# PoE_Si3404.net
KiCad netlist of a schematic drawn in Altium Designer
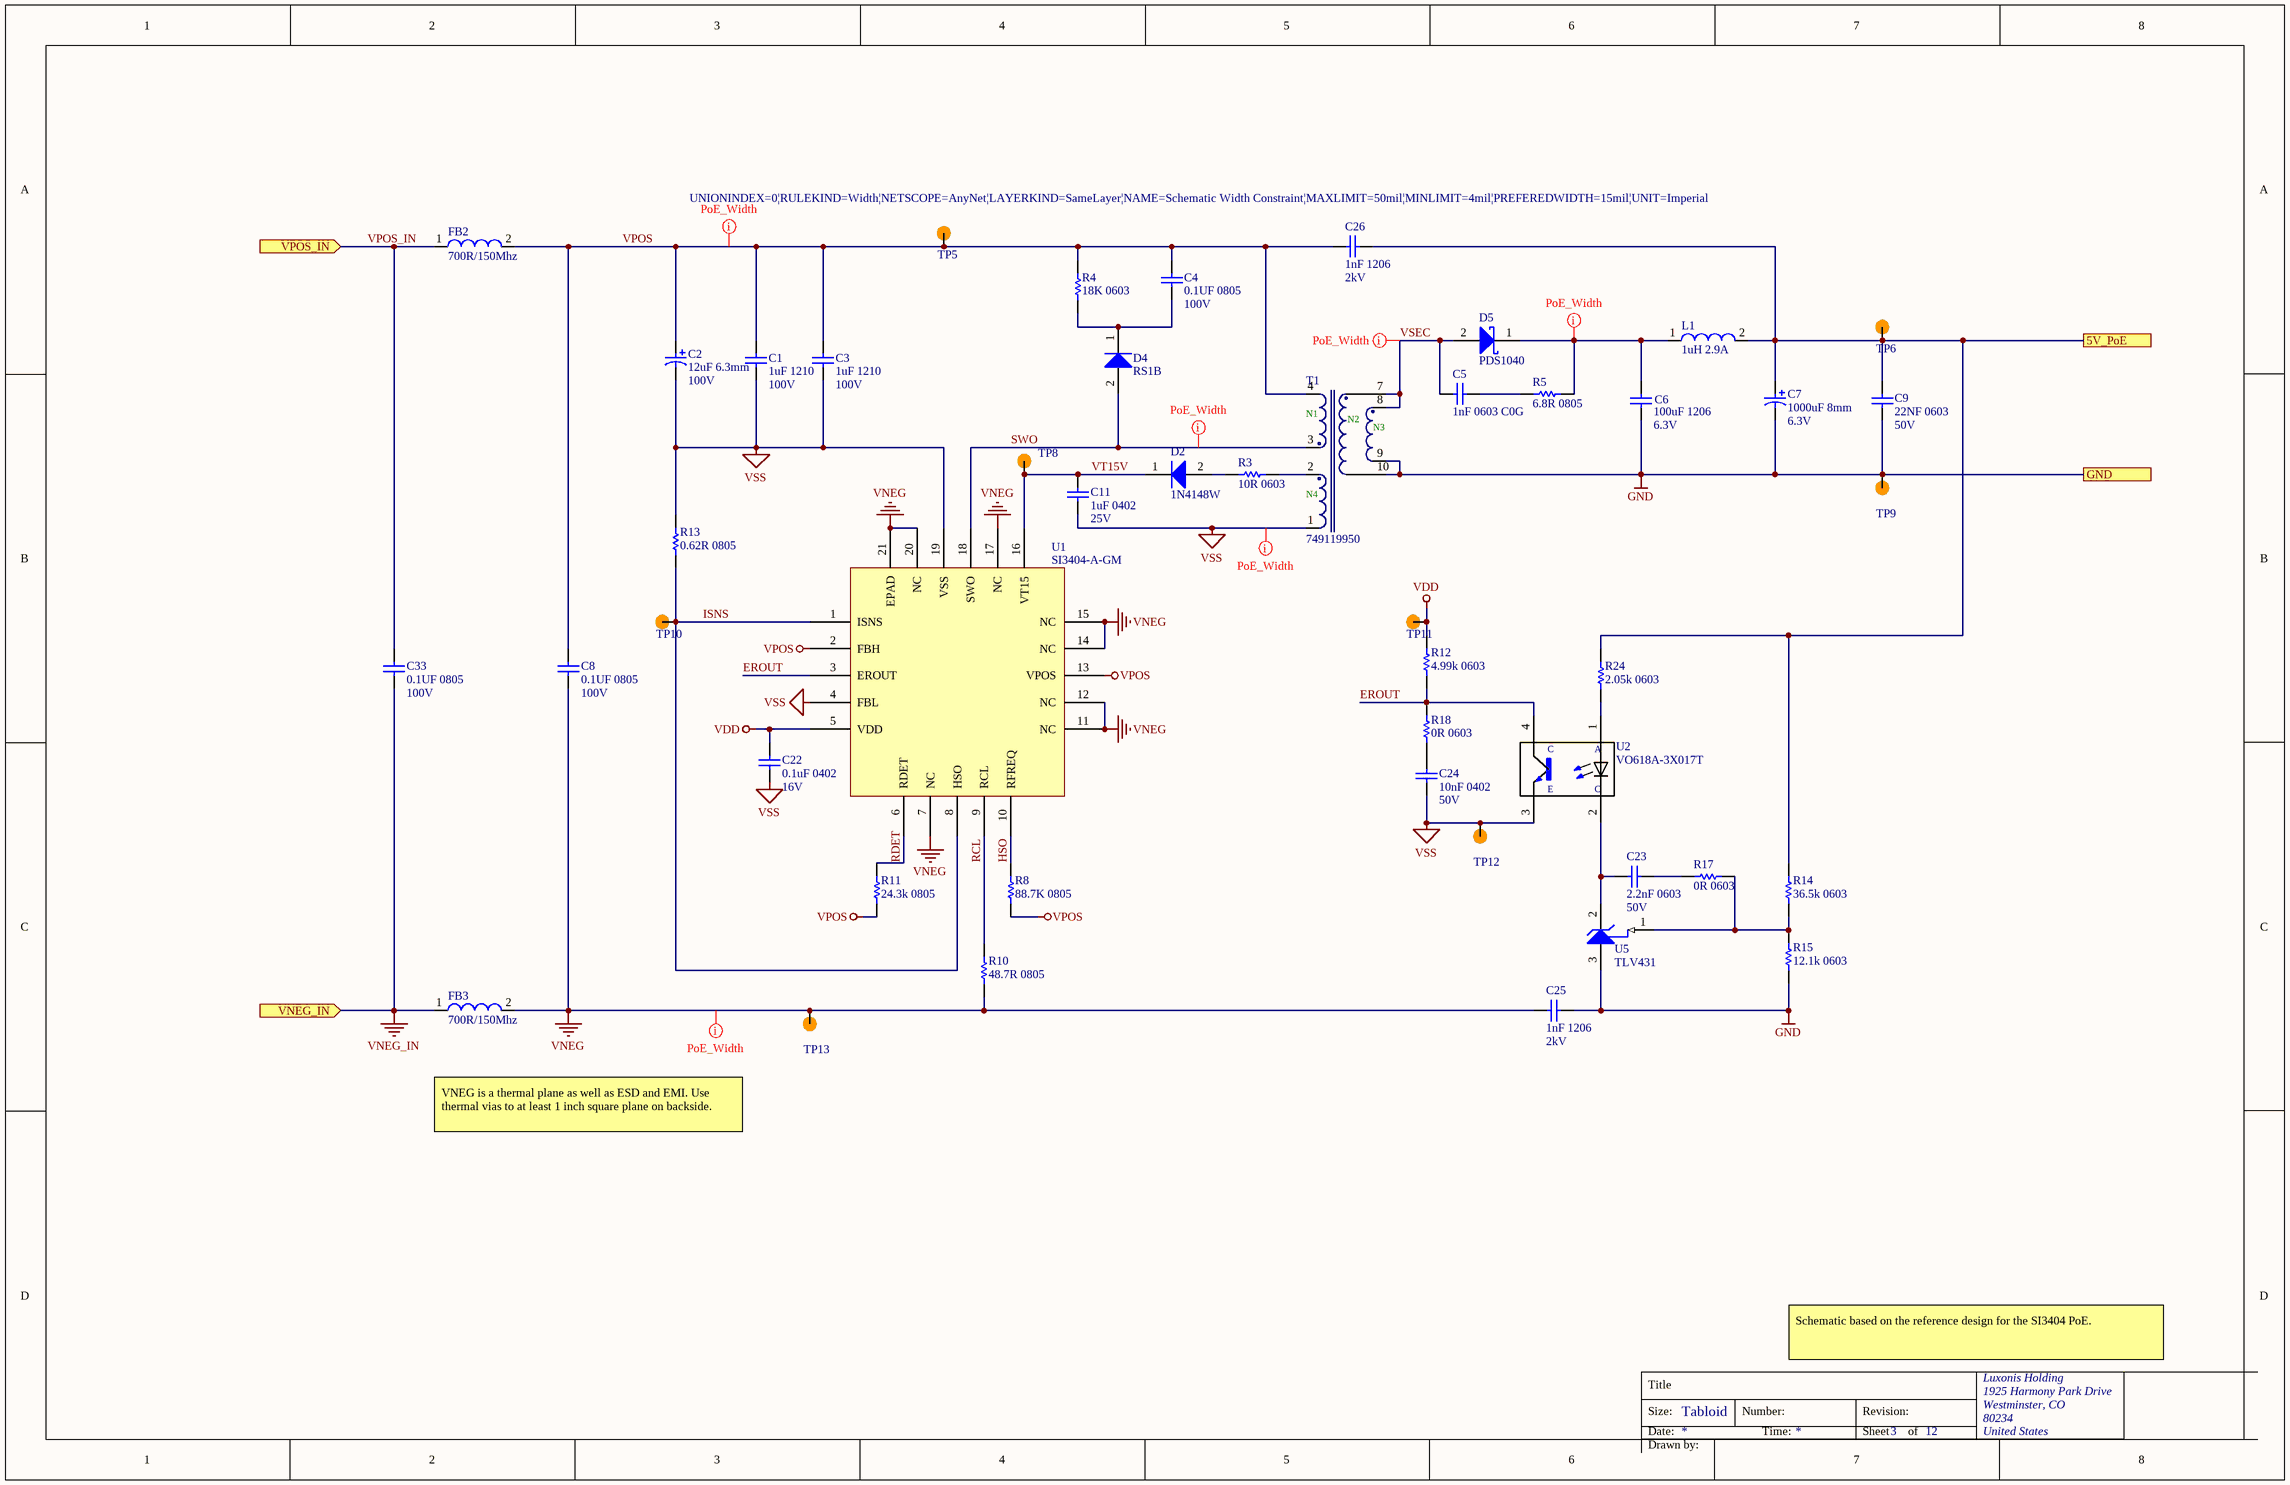
[diagram p0: PoE_Si3404.SchDoc]

(export (version "E")
  (design (tool "Eeschema 10.0.6"))
  (components
    (comp (ref "C1")
      (value "1uF 1210")
      (footprint "CAP_Altium_Vault_Generic:CAPC1210(3225)280_N")
      (description "CAP CER 1UF 100V X7R 1210")
      (fields (field (name "TOLERANCE") "10%") (field (name "VOLTAGE RATING") "100V"))
      (libsource (lib "PCBProject") (part "CL32B105KCJNNNE"))
    )
    (comp (ref "C2")
      (value "12uF 6.3mm")
      (footprint "BW2098POE:EEU-FC2A120")
      (description "CAP ALUM 12UF 20% 100V RADIAL")
      (fields (field (name "TOLERANCE") "20%") (field (name "VOLTAGE") "100V"))
      (libsource (lib "BW2098POE") (part "EEU-FC2A120"))
    )
    (comp (ref "C3")
      (value "1uF 1210")
      (footprint "CAP_Altium_Vault_Generic:CAPC1210(3225)280_N")
      (description "CAP CER 1UF 100V X7R 1210")
      (fields (field (name "TOLERANCE") "10%") (field (name "VOLTAGE RATING") "100V"))
      (libsource (lib "PCBProject") (part "CL32B105KCJNNNE"))
    )
    (comp (ref "C4")
      (value "0.1UF 0805")
      (footprint "CAP_Altium_Vault_Generic:CAPC0805(2012)145_N")
      (description "CAP CER 0.1UF 100V X7R 0805")
      (fields (field (name "TOLERANCE") "10%") (field (name "VOLTAGE RATING") "100V"))
      (libsource (lib "BW2098POE") (part "CL21B104KCFNNNE"))
    )
    (comp (ref "C5")
      (value "1nF 0603 C0G")
      (footprint "CAP_Altium_Vault_Generic:CAPC0603(1608)100_N")
      (description "CAP CER 1000PF 50V C0G/NP0 0603")
      (fields
        (field (name "MANUFACTURER") "Murata")
        (field (name "MANUFACTURER PART NUMBER") "GRM1885C1H102FA01D")
      )
      (libsource (lib "LuxonisMaster") (part "GRM1885C1H102FA01D"))
    )
    (comp (ref "C6")
      (value "100uF 1206")
      (footprint "CAP_Altium_Vault_Generic:CAPC1206(3216)190_N")
      (description "CAP CER 100UF 6.3V X5R 1206")
      (fields (field (name "TOLERANCE") "20%") (field (name "VOLTAGE") "6.3V"))
      (libsource (lib "PCBProject") (part "CL31A107MQHNNNE"))
    )
    (comp (ref "C7")
      (value "1000uF 8mm")
      (footprint "BW2098POE:ECA-0JM102")
      (description "CAP ALUM 1000UF 20% 6.3V RADIAL")
      (fields (field (name "TOLERANCE") "20%") (field (name "VOLTAGE") "6.3V"))
      (libsource (lib "BW2098POE") (part "ECA-0JM102"))
    )
    (comp (ref "C8")
      (value "0.1UF 0805")
      (footprint "CAP_Altium_Vault_Generic:CAPC0805(2012)145_N")
      (description "CAP CER 0.1UF 100V X7R 0805")
      (fields (field (name "TOLERANCE") "10%") (field (name "VOLTAGE RATING") "100V"))
      (libsource (lib "PCBProject") (part "CL21B104KCFNNNE"))
    )
    (comp (ref "C9")
      (value "22NF 0603")
      (footprint "CAP_Altium_Vault_Generic:CAPC0603(1608)100_N")
      (description "CAP CER 0.022UF 50V X7R 0603")
      (fields (field (name "TOLERANCE") "10%") (field (name "VOLTAGE") "50V"))
      (libsource (lib "LuxonisMaster") (part "C0603C223K5RACTU"))
    )
    (comp (ref "C11")
      (value "1uF 0402")
      (footprint "CAP_Altium_Vault_Generic:CAPC0402(1005)70_N")
      (description "CAP CER 1UF 25V X5R 0402 10%")
      (fields
        (field (name "TOLERANCE") "10%")
        (field (name "VOLTAGE") "25V")
        (field (name "VOLTAGE RATING") "25V")
      )
      (libsource (lib "LuxonisMaster") (part "GRM155R61E105KA12D"))
    )
    (comp (ref "C22")
      (value "0.1uF 0402")
      (footprint "CAP_Altium_Vault_Generic:CAPC0402(1005)60_N")
      (description "CAP CER 0.1UF 16V X7R 0402")
      (fields (field (name "TOLERANCE") "10%") (field (name "VOLTAGE RATING") "16V"))
      (libsource (lib "PCBProject") (part "CL05B104KO5NFNC"))
    )
    (comp (ref "C23")
      (value "2.2nF 0603")
      (footprint "CAP_Altium_Vault_Generic:CAPC0603(1608)100_N")
      (description "CAP CER 2200PF 50V C0G/NP0 0603")
      (fields (field (name "TOLERANCE") "5%") (field (name "VOLTAGE") "50V"))
      (libsource (lib "BW2098POE") (part "GRM1885C1H222JA01D"))
    )
    (comp (ref "C24")
      (value "10nF 0402")
      (footprint "CAP_Altium_Vault_Generic:CAPC0402(1005)60_N")
      (description "CAP CER 10000PF 50V X7R 0402")
      (fields
        (field (name "TOLERANCE") "10%")
        (field (name "VOLTAGE") "25V")
        (field (name "VOLTAGE RATING") "50V")
      )
      (libsource (lib "LuxonisMaster") (part "GRM155R71H103KA88D"))
    )
    (comp (ref "C25")
      (value "1nF 1206")
      (footprint "CAP_Altium_Vault_Generic:CAPC1206(3216)190_N")
      (description "CAP CER 1000PF 2KV X7R 1206")
      (fields (field (name "TOLERANCE") "10%") (field (name "VOLTAGE RATING (DC)") "2kV"))
      (libsource (lib "PCBProject") (part "C1206C102KGRACTU"))
    )
    (comp (ref "C26")
      (value "1nF 1206")
      (footprint "CAP_Altium_Vault_Generic:CAPC1206(3216)190_N")
      (description "CAP CER 1000PF 2KV X7R 1206")
      (fields (field (name "TOLERANCE") "10%") (field (name "VOLTAGE RATING (DC)") "2kV"))
      (libsource (lib "PCBProject") (part "C1206C102KGRACTU"))
    )
    (comp (ref "C33")
      (value "0.1UF 0805")
      (footprint "CAP_Altium_Vault_Generic:CAPC0805(2012)145_N")
      (description "CAP CER 0.1UF 100V X7R 0805")
      (fields (field (name "TOLERANCE") "10%") (field (name "VOLTAGE RATING") "100V"))
      (libsource (lib "PCBProject") (part "CL21B104KCFNNNE"))
    )
    (comp (ref "D2")
      (value "1N4148W")
      (footprint "BW2098POE:1N4148W-7-F")
      (description "DIODE GEN PURP 100V 300MA SOD123")
      (fields (field (name "VOLTAGE") "100V"))
      (libsource (lib "PCBProject") (part "1N4148W-7-F"))
    )
    (comp (ref "D4")
      (value "RS1B")
      (footprint "BW2098POE:RS1B")
      (description "DIODE GEN PURP 100V 1A SMA")
      (libsource (lib "BW2098POE") (part "RS1B"))
    )
    (comp (ref "D5")
      (value "PDS1040")
      (footprint "BW2098POE:PDS1040-13")
      (description "DIODE SCHOTTKY 40V 10A POWERDI5")
      (libsource (lib "PCBProject") (part "PDS1040-13"))
    )
    (comp (ref "FB2")
      (value "700R/150Mhz")
      (footprint "BW2098POE:742792040")
      (description "FERRITE BEAD 600 OHM 0805 1LN")
      (fields (field (name "TOLERANCE") "25%"))
      (libsource (lib "BW2098POE") (part "742792040"))
    )
    (comp (ref "FB3")
      (value "700R/150Mhz")
      (footprint "BW2098POE:742792040")
      (description "FERRITE BEAD 600 OHM 0805 1LN")
      (fields (field (name "TOLERANCE") "25%"))
      (libsource (lib "BW2098POE") (part "742792040"))
    )
    (comp (ref "L1")
      (value "1uH 2.9A")
      (footprint "BW2098POE:DO1608C-102MLx")
      (description "IND POWER WIREWOUND 1uH 20% 100KHz FERRITE 2.7A")
      (fields (field (name "TOLERANCE") "20%"))
      (libsource (lib "PCBProject") (part "DO1608C-102ML"))
    )
    (comp (ref "R3")
      (value "10R 0603")
      (footprint "RES_Altium_Vault_Generic:RESC0603(1608)_N")
      (description "RES SMD 10 OHM 1% 1/10W 0603")
      (fields (field (name "TOLERANCE") "1%"))
      (libsource (lib "PCBProject") (part "CRCW060310R0FKEA"))
    )
    (comp (ref "R4")
      (value "18K 0603")
      (footprint "RES_Altium_Vault_Generic:RESC0603(1608)_N")
      (description "RES SMD 18K OHM 5% 1/10W 0603")
      (fields (field (name "TOLERANCE") "5%"))
      (libsource (lib "BW2098POE") (part "RC0603JR-0718KL"))
    )
    (comp (ref "R5")
      (value "6.8R 0805")
      (footprint "RES_Altium_Vault_Generic:RESC0805(2012)_N")
      (description "RES SMD 6.8 OHM 1% 1/8W 0805")
      (fields (field (name "TOLERANCE") "1%"))
      (libsource (lib "BW2098POE") (part "RC0805FR-076R8L"))
    )
    (comp (ref "R8")
      (value "88.7K 0805")
      (footprint "RES_Altium_Vault_Generic:RESC0805(2012)_N")
      (description "RES SMD 88.7K OHM 1% 1/8W 0805")
      (fields (field (name "TOLERANCE") "1%"))
      (libsource (lib "BW2098POE") (part "CRCW080588K7FKEA"))
    )
    (comp (ref "R10")
      (value "48.7R 0805")
      (footprint "RES_Altium_Vault_Generic:RESC0805(2012)_N")
      (description "RES SMD 48.7 OHM 1% 1/8W 0805")
      (fields (field (name "TOLERANCE") "1%"))
      (libsource (lib "PCBProject") (part "RC0805FR-0748R7L"))
    )
    (comp (ref "R11")
      (value "24.3k 0805")
      (footprint "RES_Altium_Vault_Generic:RESC0805(2012)_N")
      (description "RES SMD 24.3K OHM 1% 1/8W 0805")
      (fields (field (name "TOLERANCE") "1%"))
      (libsource (lib "PCBProject") (part "CRCW080524K3FKEA"))
    )
    (comp (ref "R12")
      (value "4.99k 0603")
      (footprint "RES_Altium_Vault_Generic:RESC0603(1608)_N")
      (description "RES SMD 4.99K OHM 1% 1/10W 0603")
      (fields (field (name "TOLERANCE") "1%"))
      (libsource (lib "PCBProject") (part "RC0603FR-074K99L"))
    )
    (comp (ref "R13")
      (value "0.62R 0805")
      (footprint "RES_Altium_Vault_Generic:RESC0805(2012)_N")
      (description "RES SMD 620 MOHM 1% 1/8W 0805")
      (fields (field (name "TOLERANCE") "1%"))
      (libsource (lib "BW2098POE") (part "RL0805FR-070R62L"))
    )
    (comp (ref "R14")
      (value "36.5k 0603")
      (footprint "RES_Altium_Vault_Generic:RESC0603(1608)_N")
      (description "RES SMD 36.5K OHM 1% 1/10W 0603")
      (fields (field (name "TOLERANCE") "1%"))
      (libsource (lib "PCBProject") (part "RC0603FR-0736K5L"))
    )
    (comp (ref "R15")
      (value "12.1k 0603")
      (footprint "RES_Altium_Vault_Generic:RESC0603(1608)_N")
      (description "RES SMD 12.1K OHM 1% 1/10W 0603")
      (fields (field (name "TOLERANCE") "1%"))
      (libsource (lib "PCBProject") (part "RC0603FR-0712K1L"))
    )
    (comp (ref "R17")
      (value "0R 0603")
      (footprint "RES_Altium_Vault_Generic:RESC0603(1608)_N")
      (fields (field (name "TOLERANCE") "5%"))
      (libsource (lib "LuxonisMaster") (part "CRCW06030000Z0EA"))
    )
    (comp (ref "R18")
      (value "0R 0603")
      (footprint "RES_Altium_Vault_Generic:RESC0603(1608)_N")
      (fields (field (name "TOLERANCE") "5%"))
      (libsource (lib "LuxonisMaster") (part "CRCW06030000Z0EA"))
    )
    (comp (ref "R24")
      (value "2.05k 0603")
      (footprint "RES_Altium_Vault_Generic:RESC0603(1608)_N")
      (description "RES SMD 2.05K OHM 1% 1/10W 0603")
      (fields (field (name "TOLERANCE") "1%"))
      (libsource (lib "PCBProject") (part "RC0603FR-072K05L"))
    )
    (comp (ref "T1")
      (value "749119950")
      (footprint "BW2098POE:749119950")
      (description "TRANS FLYBACK POE 127UH SMD")
      (libsource (lib "BW2098POE") (part "749119950"))
    )
    (comp (ref "TP5")
      (value "TP100_200_NS")
      (footprint "LuxonisMaster:TP100_200_NS")
      (libsource (lib "LuxonisMaster") (part "TEST_POINT"))
    )
    (comp (ref "TP6")
      (value "TP100_200_NS")
      (footprint "LuxonisMaster:TP100_200_NS")
      (libsource (lib "LuxonisMaster") (part "TEST_POINT"))
    )
    (comp (ref "TP8")
      (value "TP100_200_NS")
      (footprint "LuxonisMaster:TP100_200_NS")
      (libsource (lib "LuxonisMaster") (part "TEST_POINT"))
    )
    (comp (ref "TP9")
      (value "TP100_200_NS")
      (footprint "LuxonisMaster:TP100_200_NS")
      (libsource (lib "LuxonisMaster") (part "TEST_POINT"))
    )
    (comp (ref "TP10")
      (value "TP100_200_NS")
      (footprint "LuxonisMaster:TP100_200_NS")
      (libsource (lib "LuxonisMaster") (part "TEST_POINT"))
    )
    (comp (ref "TP11")
      (value "TP100_200_NS")
      (footprint "LuxonisMaster:TP100_200_NS")
      (libsource (lib "LuxonisMaster") (part "TEST_POINT"))
    )
    (comp (ref "TP12")
      (value "TP100_200_NS")
      (footprint "LuxonisMaster:TP100_200_NS")
      (libsource (lib "LuxonisMaster") (part "TEST_POINT"))
    )
    (comp (ref "TP13")
      (value "TP100_200_NS")
      (footprint "LuxonisMaster:TP100_200_NS")
      (libsource (lib "LuxonisMaster") (part "TEST_POINT"))
    )
    (comp (ref "U1")
      (value "SI3404-A-GM")
      (footprint "BW2098POE:Si3404-A-GM")
      (description "IC POE CNTRL 1 CHANNEL 20QFN")
      (libsource (lib "BW2098POE") (part "SI3404-A-GM"))
    )
    (comp (ref "U2")
      (value "VO618A-3X017T")
      (footprint "BW2098POE:VO618A-3X017T")
      (description "OPTOISOLATOR 5.3KV TRANS 4-SMD")
      (libsource (lib "BW2098POE") (part "VO618A-3X017T"))
    )
    (comp (ref "U5")
      (value "TLV431")
      (footprint "BW2098POE:TLV431BCDBZR")
      (description "IC VREF SHUNT ADJ SOT23-3")
      (fields (field (name "TOLERANCE") "0.5%"))
      (libsource (lib "BW2098POE") (part "TLV431BCDBZR"))
    )
  )
  (nets
    (net (code "1") (name "/5V_PoE") (class "Default")
      (node (ref "C26") (pin "2") (pinfunction "2_2") (pintype "passive"))
      (node (ref "C7") (pin "1") (pinfunction "1_1") (pintype "passive"))
      (node (ref "C9") (pin "2") (pinfunction "2_2") (pintype "passive"))
      (node (ref "L1") (pin "2") (pinfunction "2_2") (pintype "passive"))
      (node (ref "R14") (pin "2") (pinfunction "2_2") (pintype "passive"))
      (node (ref "R24") (pin "2") (pinfunction "2_2") (pintype "passive"))
      (node (ref "TP6") (pin "1") (pintype "passive"))
    )
    (net (code "2") (name "/EROUT") (class "Default")
      (node (ref "R12") (pin "1") (pinfunction "1_1") (pintype "passive"))
      (node (ref "R18") (pin "2") (pinfunction "2_2") (pintype "passive"))
      (node (ref "U1") (pin "3") (pinfunction "EROUT_3") (pintype "passive"))
      (node (ref "U2") (pin "4") (pinfunction "CO_4") (pintype "passive"))
    )
    (net (code "3") (name "/HSO") (class "Default")
      (node (ref "R8") (pin "2") (pinfunction "2_2") (pintype "passive"))
      (node (ref "U1") (pin "10") (pinfunction "RFREQ_10") (pintype "passive"))
    )
    (net (code "4") (name "/ISNS") (class "Default")
      (node (ref "R13") (pin "1") (pinfunction "1_1") (pintype "passive"))
      (node (ref "TP10") (pin "1") (pintype "passive"))
      (node (ref "U1") (pin "1") (pinfunction "ISNS_1") (pintype "passive"))
      (node (ref "U1") (pin "8") (pinfunction "HSO_8") (pintype "passive"))
    )
    (net (code "5") (name "/RCL") (class "Default")
      (node (ref "R10") (pin "2") (pinfunction "2_2") (pintype "passive"))
      (node (ref "U1") (pin "9") (pinfunction "RCL_9") (pintype "passive"))
    )
    (net (code "6") (name "/RDET") (class "Default")
      (node (ref "R11") (pin "2") (pinfunction "2_2") (pintype "passive"))
      (node (ref "U1") (pin "6") (pinfunction "RDET_6") (pintype "passive"))
    )
    (net (code "7") (name "/SWO") (class "Default")
      (node (ref "D4") (pin "2") (pinfunction "A_2") (pintype "passive"))
      (node (ref "T1") (pin "3") (pinfunction "3_3") (pintype "passive"))
      (node (ref "U1") (pin "18") (pinfunction "SWO_18") (pintype "passive"))
    )
    (net (code "8") (name "/VPOS_IN") (class "Default")
      (node (ref "C33") (pin "2") (pinfunction "2_2") (pintype "passive"))
      (node (ref "FB2") (pin "1") (pinfunction "1_1") (pintype "passive"))
    )
    (net (code "9") (name "/VSEC") (class "Default")
      (node (ref "C5") (pin "2") (pinfunction "2_2") (pintype "passive"))
      (node (ref "D5") (pin "2") (pinfunction "A_2") (pintype "passive"))
      (node (ref "T1") (pin "7") (pinfunction "7_7") (pintype "passive"))
      (node (ref "T1") (pin "8") (pinfunction "8_8") (pintype "passive"))
    )
    (net (code "10") (name "/VT15V") (class "Default")
      (node (ref "C11") (pin "2") (pinfunction "2_2") (pintype "passive"))
      (node (ref "D2") (pin "1") (pinfunction "K_1") (pintype "passive"))
      (node (ref "TP8") (pin "1") (pintype "passive"))
      (node (ref "U1") (pin "16") (pinfunction "VT15_16") (pintype "passive"))
    )
    (net (code "11") (name "GND") (class "Default")
      (node (ref "C25") (pin "2") (pinfunction "2_2") (pintype "passive"))
      (node (ref "C6") (pin "1") (pinfunction "1_1") (pintype "passive"))
      (node (ref "C7") (pin "2") (pinfunction "2_2") (pintype "passive"))
      (node (ref "C9") (pin "1") (pinfunction "1_1") (pintype "passive"))
      (node (ref "R15") (pin "1") (pinfunction "1_1") (pintype "passive"))
      (node (ref "T1") (pin "10") (pinfunction "10_10") (pintype "passive"))
      (node (ref "T1") (pin "9") (pinfunction "9_9") (pintype "passive"))
      (node (ref "TP9") (pin "1") (pintype "passive"))
      (node (ref "U5") (pin "3") (pinfunction "ANODE_3") (pintype "passive"))
    )
    (net (code "12") (name "Net-(C5-Pad1)") (class "Default")
      (node (ref "C5") (pin "1") (pinfunction "1_1") (pintype "passive"))
      (node (ref "R5") (pin "1") (pinfunction "1_1") (pintype "passive"))
    )
    (net (code "13") (name "Net-(C23-Pad2)") (class "Default")
      (node (ref "C23") (pin "2") (pinfunction "2_2") (pintype "passive"))
      (node (ref "R17") (pin "2") (pinfunction "2_2") (pintype "passive"))
    )
    (net (code "14") (name "Net-(C24-Pad2)") (class "Default")
      (node (ref "C24") (pin "2") (pinfunction "2_2") (pintype "passive"))
      (node (ref "R18") (pin "1") (pinfunction "1_1") (pintype "passive"))
    )
    (net (code "15") (name "Net-(D2-A)") (class "Default")
      (node (ref "D2") (pin "2") (pinfunction "A_2") (pintype "passive"))
      (node (ref "R3") (pin "1") (pinfunction "1_1") (pintype "passive"))
    )
    (net (code "16") (name "Net-(D4-K)") (class "Default")
      (node (ref "C4") (pin "1") (pinfunction "1_1") (pintype "passive"))
      (node (ref "D4") (pin "1") (pinfunction "K_1") (pintype "passive"))
      (node (ref "R4") (pin "1") (pinfunction "1_1") (pintype "passive"))
    )
    (net (code "17") (name "Net-(D5-K)") (class "Default")
      (node (ref "C6") (pin "2") (pinfunction "2_2") (pintype "passive"))
      (node (ref "D5") (pin "1") (pinfunction "K_1") (pintype "passive"))
      (node (ref "L1") (pin "1") (pinfunction "1_1") (pintype "passive"))
      (node (ref "R5") (pin "2") (pinfunction "2_2") (pintype "passive"))
    )
    (net (code "18") (name "Net-(R3-Pad2)") (class "Default")
      (node (ref "R3") (pin "2") (pinfunction "2_2") (pintype "passive"))
      (node (ref "T1") (pin "2") (pinfunction "2_2") (pintype "passive"))
    )
    (net (code "19") (name "Net-(U2-A)") (class "Default")
      (node (ref "R24") (pin "1") (pinfunction "1_1") (pintype "passive"))
      (node (ref "U2") (pin "1") (pinfunction "A_1") (pintype "passive"))
    )
    (net (code "20") (name "Net-(U2-C)") (class "Default")
      (node (ref "C23") (pin "1") (pinfunction "1_1") (pintype "passive"))
      (node (ref "U2") (pin "2") (pinfunction "C_2") (pintype "passive"))
      (node (ref "U5") (pin "2") (pinfunction "CATHODE_2") (pintype "passive"))
    )
    (net (code "21") (name "Net-(U5-REF)") (class "Default")
      (node (ref "R14") (pin "1") (pinfunction "1_1") (pintype "passive"))
      (node (ref "R15") (pin "2") (pinfunction "2_2") (pintype "passive"))
      (node (ref "R17") (pin "1") (pinfunction "1_1") (pintype "passive"))
      (node (ref "U5") (pin "1") (pinfunction "REF_1") (pintype "input"))
    )
    (net (code "22") (name "VDD") (class "Default")
      (node (ref "C22") (pin "2") (pinfunction "2_2") (pintype "passive"))
      (node (ref "R12") (pin "2") (pinfunction "2_2") (pintype "passive"))
      (node (ref "TP11") (pin "1") (pintype "passive"))
      (node (ref "U1") (pin "5") (pinfunction "VDD_5") (pintype "passive"))
    )
    (net (code "23") (name "VNEG") (class "Default")
      (node (ref "C25") (pin "1") (pinfunction "1_1") (pintype "passive"))
      (node (ref "C8") (pin "1") (pinfunction "1_1") (pintype "passive"))
      (node (ref "FB3") (pin "2") (pinfunction "2_2") (pintype "passive"))
      (node (ref "R10") (pin "1") (pinfunction "1_1") (pintype "passive"))
      (node (ref "TP13") (pin "1") (pintype "passive"))
      (node (ref "U1") (pin "11") (pinfunction "NC_11") (pintype "passive"))
      (node (ref "U1") (pin "12") (pinfunction "NC_12") (pintype "passive"))
      (node (ref "U1") (pin "14") (pinfunction "NC_14") (pintype "passive"))
      (node (ref "U1") (pin "15") (pinfunction "NC_15") (pintype "passive"))
      (node (ref "U1") (pin "17") (pinfunction "NC_17") (pintype "passive"))
      (node (ref "U1") (pin "20") (pinfunction "NC_20") (pintype "passive"))
      (node (ref "U1") (pin "21") (pinfunction "EPAD_21") (pintype "passive"))
      (node (ref "U1") (pin "7") (pinfunction "NC_7") (pintype "passive"))
    )
    (net (code "24") (name "VNEG_IN") (class "Default")
      (node (ref "C33") (pin "1") (pinfunction "1_1") (pintype "passive"))
      (node (ref "FB3") (pin "1") (pinfunction "1_1") (pintype "passive"))
    )
    (net (code "25") (name "VPOS") (class "Default")
      (node (ref "C1") (pin "2") (pinfunction "2_2") (pintype "passive"))
      (node (ref "C2") (pin "1") (pinfunction "1_1") (pintype "passive"))
      (node (ref "C26") (pin "1") (pinfunction "1_1") (pintype "passive"))
      (node (ref "C3") (pin "2") (pinfunction "2_2") (pintype "passive"))
      (node (ref "C4") (pin "2") (pinfunction "2_2") (pintype "passive"))
      (node (ref "C8") (pin "2") (pinfunction "2_2") (pintype "passive"))
      (node (ref "FB2") (pin "2") (pinfunction "2_2") (pintype "passive"))
      (node (ref "R11") (pin "1") (pinfunction "1_1") (pintype "passive"))
      (node (ref "R4") (pin "2") (pinfunction "2_2") (pintype "passive"))
      (node (ref "R8") (pin "1") (pinfunction "1_1") (pintype "passive"))
      (node (ref "T1") (pin "4") (pinfunction "4_4") (pintype "passive"))
      (node (ref "TP5") (pin "1") (pintype "passive"))
      (node (ref "U1") (pin "13") (pinfunction "VPOS_13") (pintype "passive"))
      (node (ref "U1") (pin "2") (pinfunction "FBH_2") (pintype "passive"))
    )
    (net (code "26") (name "VSS") (class "Default")
      (node (ref "C1") (pin "1") (pinfunction "1_1") (pintype "passive"))
      (node (ref "C11") (pin "1") (pinfunction "1_1") (pintype "passive"))
      (node (ref "C2") (pin "2") (pinfunction "2_2") (pintype "passive"))
      (node (ref "C22") (pin "1") (pinfunction "1_1") (pintype "passive"))
      (node (ref "C24") (pin "1") (pinfunction "1_1") (pintype "passive"))
      (node (ref "C3") (pin "1") (pinfunction "1_1") (pintype "passive"))
      (node (ref "R13") (pin "2") (pinfunction "2_2") (pintype "passive"))
      (node (ref "T1") (pin "1") (pinfunction "1_1") (pintype "passive"))
      (node (ref "TP12") (pin "1") (pintype "passive"))
      (node (ref "U1") (pin "19") (pinfunction "VSS_19") (pintype "passive"))
      (node (ref "U1") (pin "4") (pinfunction "FBL_4") (pintype "passive"))
      (node (ref "U2") (pin "3") (pinfunction "E_3") (pintype "passive"))
    )
  )
)
